# 16-pin_SOIC_TSSOP.net
KiCad netlist of a schematic drawn in EAGLE
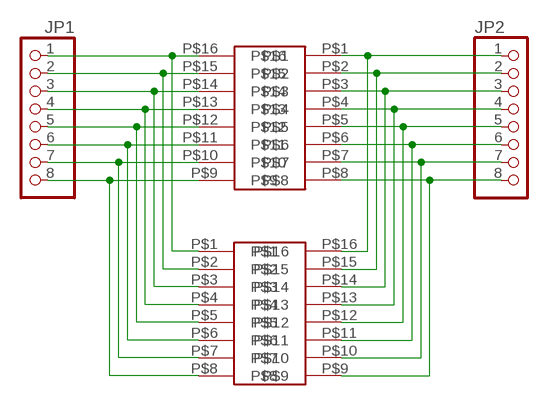
[diagram p0: schematic, sheet 1]

(export (version "E")
  (design (tool "Eeschema 10.0.6"))
  (components
    (comp (ref "JP1")
      (value "PADS-8CLEANBIG")
      (footprint "eagle-import:PADS-8")
      (libsource (lib "eagle-import") (part "PADS-8CLEANBIG"))
    )
    (comp (ref "JP2")
      (value "PADS-8CLEANBIG")
      (footprint "eagle-import:PADS-8")
      (libsource (lib "eagle-import") (part "PADS-8CLEANBIG"))
    )
    (comp (ref "U$1")
      (value "16-PINSOIC-NW")
      (footprint "eagle-import:SO16-NW")
      (libsource (lib "eagle-import") (part "16-PINSOIC-NW"))
    )
    (comp (ref "U$2")
      (value "16-PINTSSOP-NW")
      (footprint "eagle-import:TSSOP16-NW")
      (libsource (lib "eagle-import") (part "16-PINTSSOP-NW"))
    )
  )
  (nets
    (net (code "1") (name "Net-(JP1-Pad1)") (class "Default")
      (node (ref "JP1") (pin "1") (pinfunction "1_1") (pintype "passive"))
      (node (ref "U$1") (pin "P$1") (pinfunction "P$1_P$1") (pintype "bidirectional"))
      (node (ref "U$2") (pin "P$16") (pinfunction "P$16_P$16") (pintype "bidirectional"))
    )
    (net (code "2") (name "Net-(JP1-Pad2)") (class "Default")
      (node (ref "JP1") (pin "2") (pinfunction "2_2") (pintype "passive"))
      (node (ref "U$1") (pin "P$2") (pinfunction "P$2_P$2") (pintype "bidirectional"))
      (node (ref "U$2") (pin "P$15") (pinfunction "P$15_P$15") (pintype "bidirectional"))
    )
    (net (code "3") (name "Net-(JP1-Pad3)") (class "Default")
      (node (ref "JP1") (pin "3") (pinfunction "3_3") (pintype "passive"))
      (node (ref "U$1") (pin "P$3") (pinfunction "P$3_P$3") (pintype "bidirectional"))
      (node (ref "U$2") (pin "P$14") (pinfunction "P$14_P$14") (pintype "bidirectional"))
    )
    (net (code "4") (name "Net-(JP1-Pad4)") (class "Default")
      (node (ref "JP1") (pin "4") (pinfunction "4_4") (pintype "passive"))
      (node (ref "U$1") (pin "P$4") (pinfunction "P$4_P$4") (pintype "bidirectional"))
      (node (ref "U$2") (pin "P$13") (pinfunction "P$13_P$13") (pintype "bidirectional"))
    )
    (net (code "5") (name "Net-(JP1-Pad5)") (class "Default")
      (node (ref "JP1") (pin "5") (pinfunction "5_5") (pintype "passive"))
      (node (ref "U$1") (pin "P$5") (pinfunction "P$5_P$5") (pintype "bidirectional"))
      (node (ref "U$2") (pin "P$12") (pinfunction "P$12_P$12") (pintype "bidirectional"))
    )
    (net (code "6") (name "Net-(JP1-Pad6)") (class "Default")
      (node (ref "JP1") (pin "6") (pinfunction "6_6") (pintype "passive"))
      (node (ref "U$1") (pin "P$6") (pinfunction "P$6_P$6") (pintype "bidirectional"))
      (node (ref "U$2") (pin "P$11") (pinfunction "P$11_P$11") (pintype "bidirectional"))
    )
    (net (code "7") (name "Net-(JP1-Pad7)") (class "Default")
      (node (ref "JP1") (pin "7") (pinfunction "7_7") (pintype "passive"))
      (node (ref "U$1") (pin "P$7") (pinfunction "P$7_P$7") (pintype "bidirectional"))
      (node (ref "U$2") (pin "P$10") (pinfunction "P$10_P$10") (pintype "bidirectional"))
    )
    (net (code "8") (name "Net-(JP1-Pad8)") (class "Default")
      (node (ref "JP1") (pin "8") (pinfunction "8_8") (pintype "passive"))
      (node (ref "U$1") (pin "P$8") (pinfunction "P$8_P$8") (pintype "bidirectional"))
      (node (ref "U$2") (pin "P$9") (pinfunction "P$9_P$9") (pintype "bidirectional"))
    )
    (net (code "9") (name "Net-(JP2-Pad1)") (class "Default")
      (node (ref "JP2") (pin "1") (pinfunction "1_1") (pintype "passive"))
      (node (ref "U$1") (pin "P$16") (pinfunction "P$16_P$16") (pintype "bidirectional"))
      (node (ref "U$2") (pin "P$1") (pinfunction "P$1_P$1") (pintype "bidirectional"))
    )
    (net (code "10") (name "Net-(JP2-Pad2)") (class "Default")
      (node (ref "JP2") (pin "2") (pinfunction "2_2") (pintype "passive"))
      (node (ref "U$1") (pin "P$15") (pinfunction "P$15_P$15") (pintype "bidirectional"))
      (node (ref "U$2") (pin "P$2") (pinfunction "P$2_P$2") (pintype "bidirectional"))
    )
    (net (code "11") (name "Net-(JP2-Pad3)") (class "Default")
      (node (ref "JP2") (pin "3") (pinfunction "3_3") (pintype "passive"))
      (node (ref "U$1") (pin "P$14") (pinfunction "P$14_P$14") (pintype "bidirectional"))
      (node (ref "U$2") (pin "P$3") (pinfunction "P$3_P$3") (pintype "bidirectional"))
    )
    (net (code "12") (name "Net-(JP2-Pad4)") (class "Default")
      (node (ref "JP2") (pin "4") (pinfunction "4_4") (pintype "passive"))
      (node (ref "U$1") (pin "P$13") (pinfunction "P$13_P$13") (pintype "bidirectional"))
      (node (ref "U$2") (pin "P$4") (pinfunction "P$4_P$4") (pintype "bidirectional"))
    )
    (net (code "13") (name "Net-(JP2-Pad5)") (class "Default")
      (node (ref "JP2") (pin "5") (pinfunction "5_5") (pintype "passive"))
      (node (ref "U$1") (pin "P$12") (pinfunction "P$12_P$12") (pintype "bidirectional"))
      (node (ref "U$2") (pin "P$5") (pinfunction "P$5_P$5") (pintype "bidirectional"))
    )
    (net (code "14") (name "Net-(JP2-Pad6)") (class "Default")
      (node (ref "JP2") (pin "6") (pinfunction "6_6") (pintype "passive"))
      (node (ref "U$1") (pin "P$11") (pinfunction "P$11_P$11") (pintype "bidirectional"))
      (node (ref "U$2") (pin "P$6") (pinfunction "P$6_P$6") (pintype "bidirectional"))
    )
    (net (code "15") (name "Net-(JP2-Pad7)") (class "Default")
      (node (ref "JP2") (pin "7") (pinfunction "7_7") (pintype "passive"))
      (node (ref "U$1") (pin "P$10") (pinfunction "P$10_P$10") (pintype "bidirectional"))
      (node (ref "U$2") (pin "P$7") (pinfunction "P$7_P$7") (pintype "bidirectional"))
    )
    (net (code "16") (name "Net-(JP2-Pad8)") (class "Default")
      (node (ref "JP2") (pin "8") (pinfunction "8_8") (pintype "passive"))
      (node (ref "U$1") (pin "P$9") (pinfunction "P$9_P$9") (pintype "bidirectional"))
      (node (ref "U$2") (pin "P$8") (pinfunction "P$8_P$8") (pintype "bidirectional"))
    )
  )
)
